# Driver.net
KiCad netlist of a schematic drawn in Altium Designer
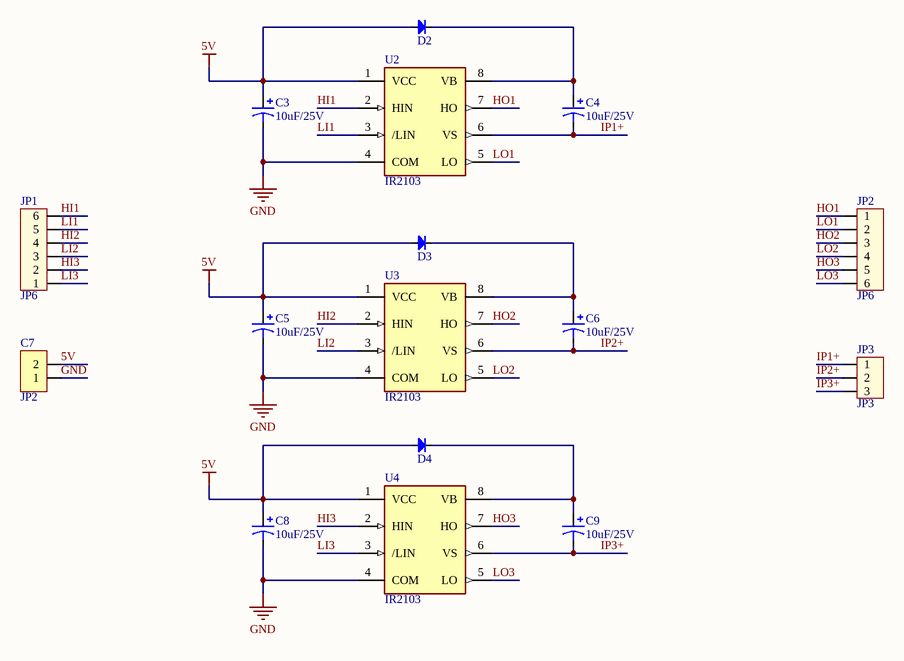
[diagram p0: Driver.SchDoc]

(export (version "E")
  (design (tool "Eeschema 10.0.6"))
  (components
    (comp (ref "C3")
      (value "10uF/25V")
      (footprint "C3MM")
      (description "Polarized Capacitor (Axial)")
      (fields (field (name "PUBLISHER") "Altium Limited"))
      (libsource (lib "My Library_1") (part "Cap Pol"))
    )
    (comp (ref "C4")
      (value "10uF/25V")
      (footprint "C3MM")
      (description "Polarized Capacitor (Axial)")
      (fields (field (name "PUBLISHER") "Altium Limited"))
      (libsource (lib "My Library_1") (part "Cap Pol"))
    )
    (comp (ref "C5")
      (value "10uF/25V")
      (footprint "C3MM")
      (description "Polarized Capacitor (Axial)")
      (fields (field (name "PUBLISHER") "Altium Limited"))
      (libsource (lib "My Library_1") (part "Cap Pol"))
    )
    (comp (ref "C6")
      (value "10uF/25V")
      (footprint "C3MM")
      (description "Polarized Capacitor (Axial)")
      (fields (field (name "PUBLISHER") "Altium Limited"))
      (libsource (lib "My Library_1") (part "Cap Pol"))
    )
    (comp (ref "C7")
      (value "JP2")
      (footprint "JP2-C1T")
      (description "WR-PHD 2.54 mm Angled Socket Header")
      (fields
        (field (name "MANUFACTURER") "Würth Elektronik eiSos GmbH")
        (field (name "PARTNO") "613002143121")
        (field (name "CREATED BY") "Karrer Zheng")
      )
      (libsource (lib "My Library_1") (part "JP2"))
    )
    (comp (ref "C8")
      (value "10uF/25V")
      (footprint "C3MM")
      (description "Polarized Capacitor (Axial)")
      (fields (field (name "PUBLISHER") "Altium Limited"))
      (libsource (lib "My Library_1") (part "Cap Pol"))
    )
    (comp (ref "C9")
      (value "10uF/25V")
      (footprint "C3MM")
      (description "Polarized Capacitor (Axial)")
      (fields (field (name "PUBLISHER") "Altium Limited"))
      (libsource (lib "My Library_1") (part "Cap Pol"))
    )
    (comp (ref "D2")
      (value "Diode")
      (footprint "DIO-1A")
      (description "Default Diode")
      (fields (field (name "PUBLISHER") "Altium Limited"))
      (libsource (lib "My Library_1") (part "Diode"))
    )
    (comp (ref "D3")
      (value "Diode")
      (footprint "DIO-1A")
      (description "Default Diode")
      (fields (field (name "PUBLISHER") "Altium Limited"))
      (libsource (lib "My Library_1") (part "Diode"))
    )
    (comp (ref "D4")
      (value "Diode")
      (footprint "DIO-1A")
      (description "Default Diode")
      (fields (field (name "PUBLISHER") "Altium Limited"))
      (libsource (lib "My Library_1") (part "Diode"))
    )
    (comp (ref "JP1")
      (value "JP6")
      (footprint "CON6")
      (description "Connector 6")
      (libsource (lib "") (part "Con6_1"))
    )
    (comp (ref "JP2")
      (value "JP6")
      (footprint "CON6")
      (description "Connector 6")
      (libsource (lib "My Library_1") (part "Con6"))
    )
    (comp (ref "JP3")
      (value "JP3")
      (footprint "CON3")
      (description "Connector 3")
      (libsource (lib "My Library_1") (part "Con3"))
    )
    (comp (ref "U2")
      (value "IR2103")
      (footprint "DIL08")
      (description "Half-Bridge Gate Driver IC Inverting, Non-Inverting 8-PDIP")
      (fields (field (name "MF") "Infineon"))
      (libsource (lib "IR2103") (part "IR2103"))
    )
    (comp (ref "U3")
      (value "IR2103")
      (footprint "DIL08")
      (description "Half-Bridge Gate Driver IC Inverting, Non-Inverting 8-PDIP")
      (fields (field (name "MF") "Infineon"))
      (libsource (lib "IR2103") (part "IR2103"))
    )
    (comp (ref "U4")
      (value "IR2103")
      (footprint "DIL08")
      (description "Half-Bridge Gate Driver IC Inverting, Non-Inverting 8-PDIP")
      (fields (field (name "MF") "Infineon"))
      (libsource (lib "IR2103") (part "IR2103"))
    )
  )
  (nets
    (net (code "1") (name "/HI1") (class "Default")
      (node (ref "JP1") (pin "6") (pinfunction "6_6") (pintype "passive"))
      (node (ref "U2") (pin "2") (pinfunction "HIN_2") (pintype "input"))
    )
    (net (code "2") (name "/HI2") (class "Default")
      (node (ref "JP1") (pin "4") (pinfunction "4_4") (pintype "passive"))
      (node (ref "U3") (pin "2") (pinfunction "HIN_2") (pintype "input"))
    )
    (net (code "3") (name "/HI3") (class "Default")
      (node (ref "JP1") (pin "2") (pinfunction "2_2") (pintype "passive"))
      (node (ref "U4") (pin "2") (pinfunction "HIN_2") (pintype "input"))
    )
    (net (code "4") (name "/HO1") (class "Default")
      (node (ref "JP2") (pin "1") (pinfunction "1_1") (pintype "passive"))
      (node (ref "U2") (pin "7") (pinfunction "HO_7") (pintype "output"))
    )
    (net (code "5") (name "/HO2") (class "Default")
      (node (ref "JP2") (pin "3") (pinfunction "3_3") (pintype "passive"))
      (node (ref "U3") (pin "7") (pinfunction "HO_7") (pintype "output"))
    )
    (net (code "6") (name "/HO3") (class "Default")
      (node (ref "JP2") (pin "5") (pinfunction "5_5") (pintype "passive"))
      (node (ref "U4") (pin "7") (pinfunction "HO_7") (pintype "output"))
    )
    (net (code "7") (name "/IP1+") (class "Default")
      (node (ref "C4") (pin "2") (pinfunction "2_2") (pintype "passive"))
      (node (ref "JP3") (pin "1") (pinfunction "1_1") (pintype "passive"))
      (node (ref "U2") (pin "6") (pinfunction "VS_6") (pintype "output"))
    )
    (net (code "8") (name "/IP2+") (class "Default")
      (node (ref "C6") (pin "2") (pinfunction "2_2") (pintype "passive"))
      (node (ref "JP3") (pin "2") (pinfunction "2_2") (pintype "passive"))
      (node (ref "U3") (pin "6") (pinfunction "VS_6") (pintype "output"))
    )
    (net (code "9") (name "/IP3+") (class "Default")
      (node (ref "C9") (pin "2") (pinfunction "2_2") (pintype "passive"))
      (node (ref "JP3") (pin "3") (pinfunction "3_3") (pintype "passive"))
      (node (ref "U4") (pin "6") (pinfunction "VS_6") (pintype "output"))
    )
    (net (code "10") (name "/LI1") (class "Default")
      (node (ref "JP1") (pin "5") (pinfunction "5_5") (pintype "passive"))
      (node (ref "U2") (pin "3") (pinfunction "/LIN_3") (pintype "input"))
    )
    (net (code "11") (name "/LI2") (class "Default")
      (node (ref "JP1") (pin "3") (pinfunction "3_3") (pintype "passive"))
      (node (ref "U3") (pin "3") (pinfunction "/LIN_3") (pintype "input"))
    )
    (net (code "12") (name "/LI3") (class "Default")
      (node (ref "JP1") (pin "1") (pinfunction "1_1") (pintype "passive"))
      (node (ref "U4") (pin "3") (pinfunction "/LIN_3") (pintype "input"))
    )
    (net (code "13") (name "/LO1") (class "Default")
      (node (ref "JP2") (pin "2") (pinfunction "2_2") (pintype "passive"))
      (node (ref "U2") (pin "5") (pinfunction "LO_5") (pintype "output"))
    )
    (net (code "14") (name "/LO2") (class "Default")
      (node (ref "JP2") (pin "4") (pinfunction "4_4") (pintype "passive"))
      (node (ref "U3") (pin "5") (pinfunction "LO_5") (pintype "output"))
    )
    (net (code "15") (name "/LO3") (class "Default")
      (node (ref "JP2") (pin "6") (pinfunction "6_6") (pintype "passive"))
      (node (ref "U4") (pin "5") (pinfunction "LO_5") (pintype "output"))
    )
    (net (code "16") (name "5V") (class "Default")
      (node (ref "C3") (pin "1") (pinfunction "1_1") (pintype "passive"))
      (node (ref "C5") (pin "1") (pinfunction "1_1") (pintype "passive"))
      (node (ref "C7") (pin "2") (pinfunction "2_2") (pintype "passive"))
      (node (ref "C8") (pin "1") (pinfunction "1_1") (pintype "passive"))
      (node (ref "D2") (pin "1") (pinfunction "A_1") (pintype "passive"))
      (node (ref "D3") (pin "1") (pinfunction "A_1") (pintype "passive"))
      (node (ref "D4") (pin "1") (pinfunction "A_1") (pintype "passive"))
      (node (ref "U2") (pin "1") (pinfunction "VCC_1") (pintype "power_in"))
      (node (ref "U3") (pin "1") (pinfunction "VCC_1") (pintype "power_in"))
      (node (ref "U4") (pin "1") (pinfunction "VCC_1") (pintype "power_in"))
    )
    (net (code "17") (name "GND") (class "Default")
      (node (ref "C3") (pin "2") (pinfunction "2_2") (pintype "passive"))
      (node (ref "C5") (pin "2") (pinfunction "2_2") (pintype "passive"))
      (node (ref "C7") (pin "1") (pinfunction "1_1") (pintype "passive"))
      (node (ref "C8") (pin "2") (pinfunction "2_2") (pintype "passive"))
      (node (ref "U2") (pin "4") (pinfunction "COM_4") (pintype "power_in"))
      (node (ref "U3") (pin "4") (pinfunction "COM_4") (pintype "power_in"))
      (node (ref "U4") (pin "4") (pinfunction "COM_4") (pintype "power_in"))
    )
    (net (code "18") (name "Net-(D2-K)") (class "Default")
      (node (ref "C4") (pin "1") (pinfunction "1_1") (pintype "passive"))
      (node (ref "D2") (pin "2") (pinfunction "K_2") (pintype "passive"))
      (node (ref "U2") (pin "8") (pinfunction "VB_8") (pintype "power_in"))
    )
    (net (code "19") (name "Net-(D3-K)") (class "Default")
      (node (ref "C6") (pin "1") (pinfunction "1_1") (pintype "passive"))
      (node (ref "D3") (pin "2") (pinfunction "K_2") (pintype "passive"))
      (node (ref "U3") (pin "8") (pinfunction "VB_8") (pintype "power_in"))
    )
    (net (code "20") (name "Net-(D4-K)") (class "Default")
      (node (ref "C9") (pin "1") (pinfunction "1_1") (pintype "passive"))
      (node (ref "D4") (pin "2") (pinfunction "K_2") (pintype "passive"))
      (node (ref "U4") (pin "8") (pinfunction "VB_8") (pintype "power_in"))
    )
  )
)
